# SCH_Usbhub.net
KiCad netlist of a schematic drawn in EasyEDA
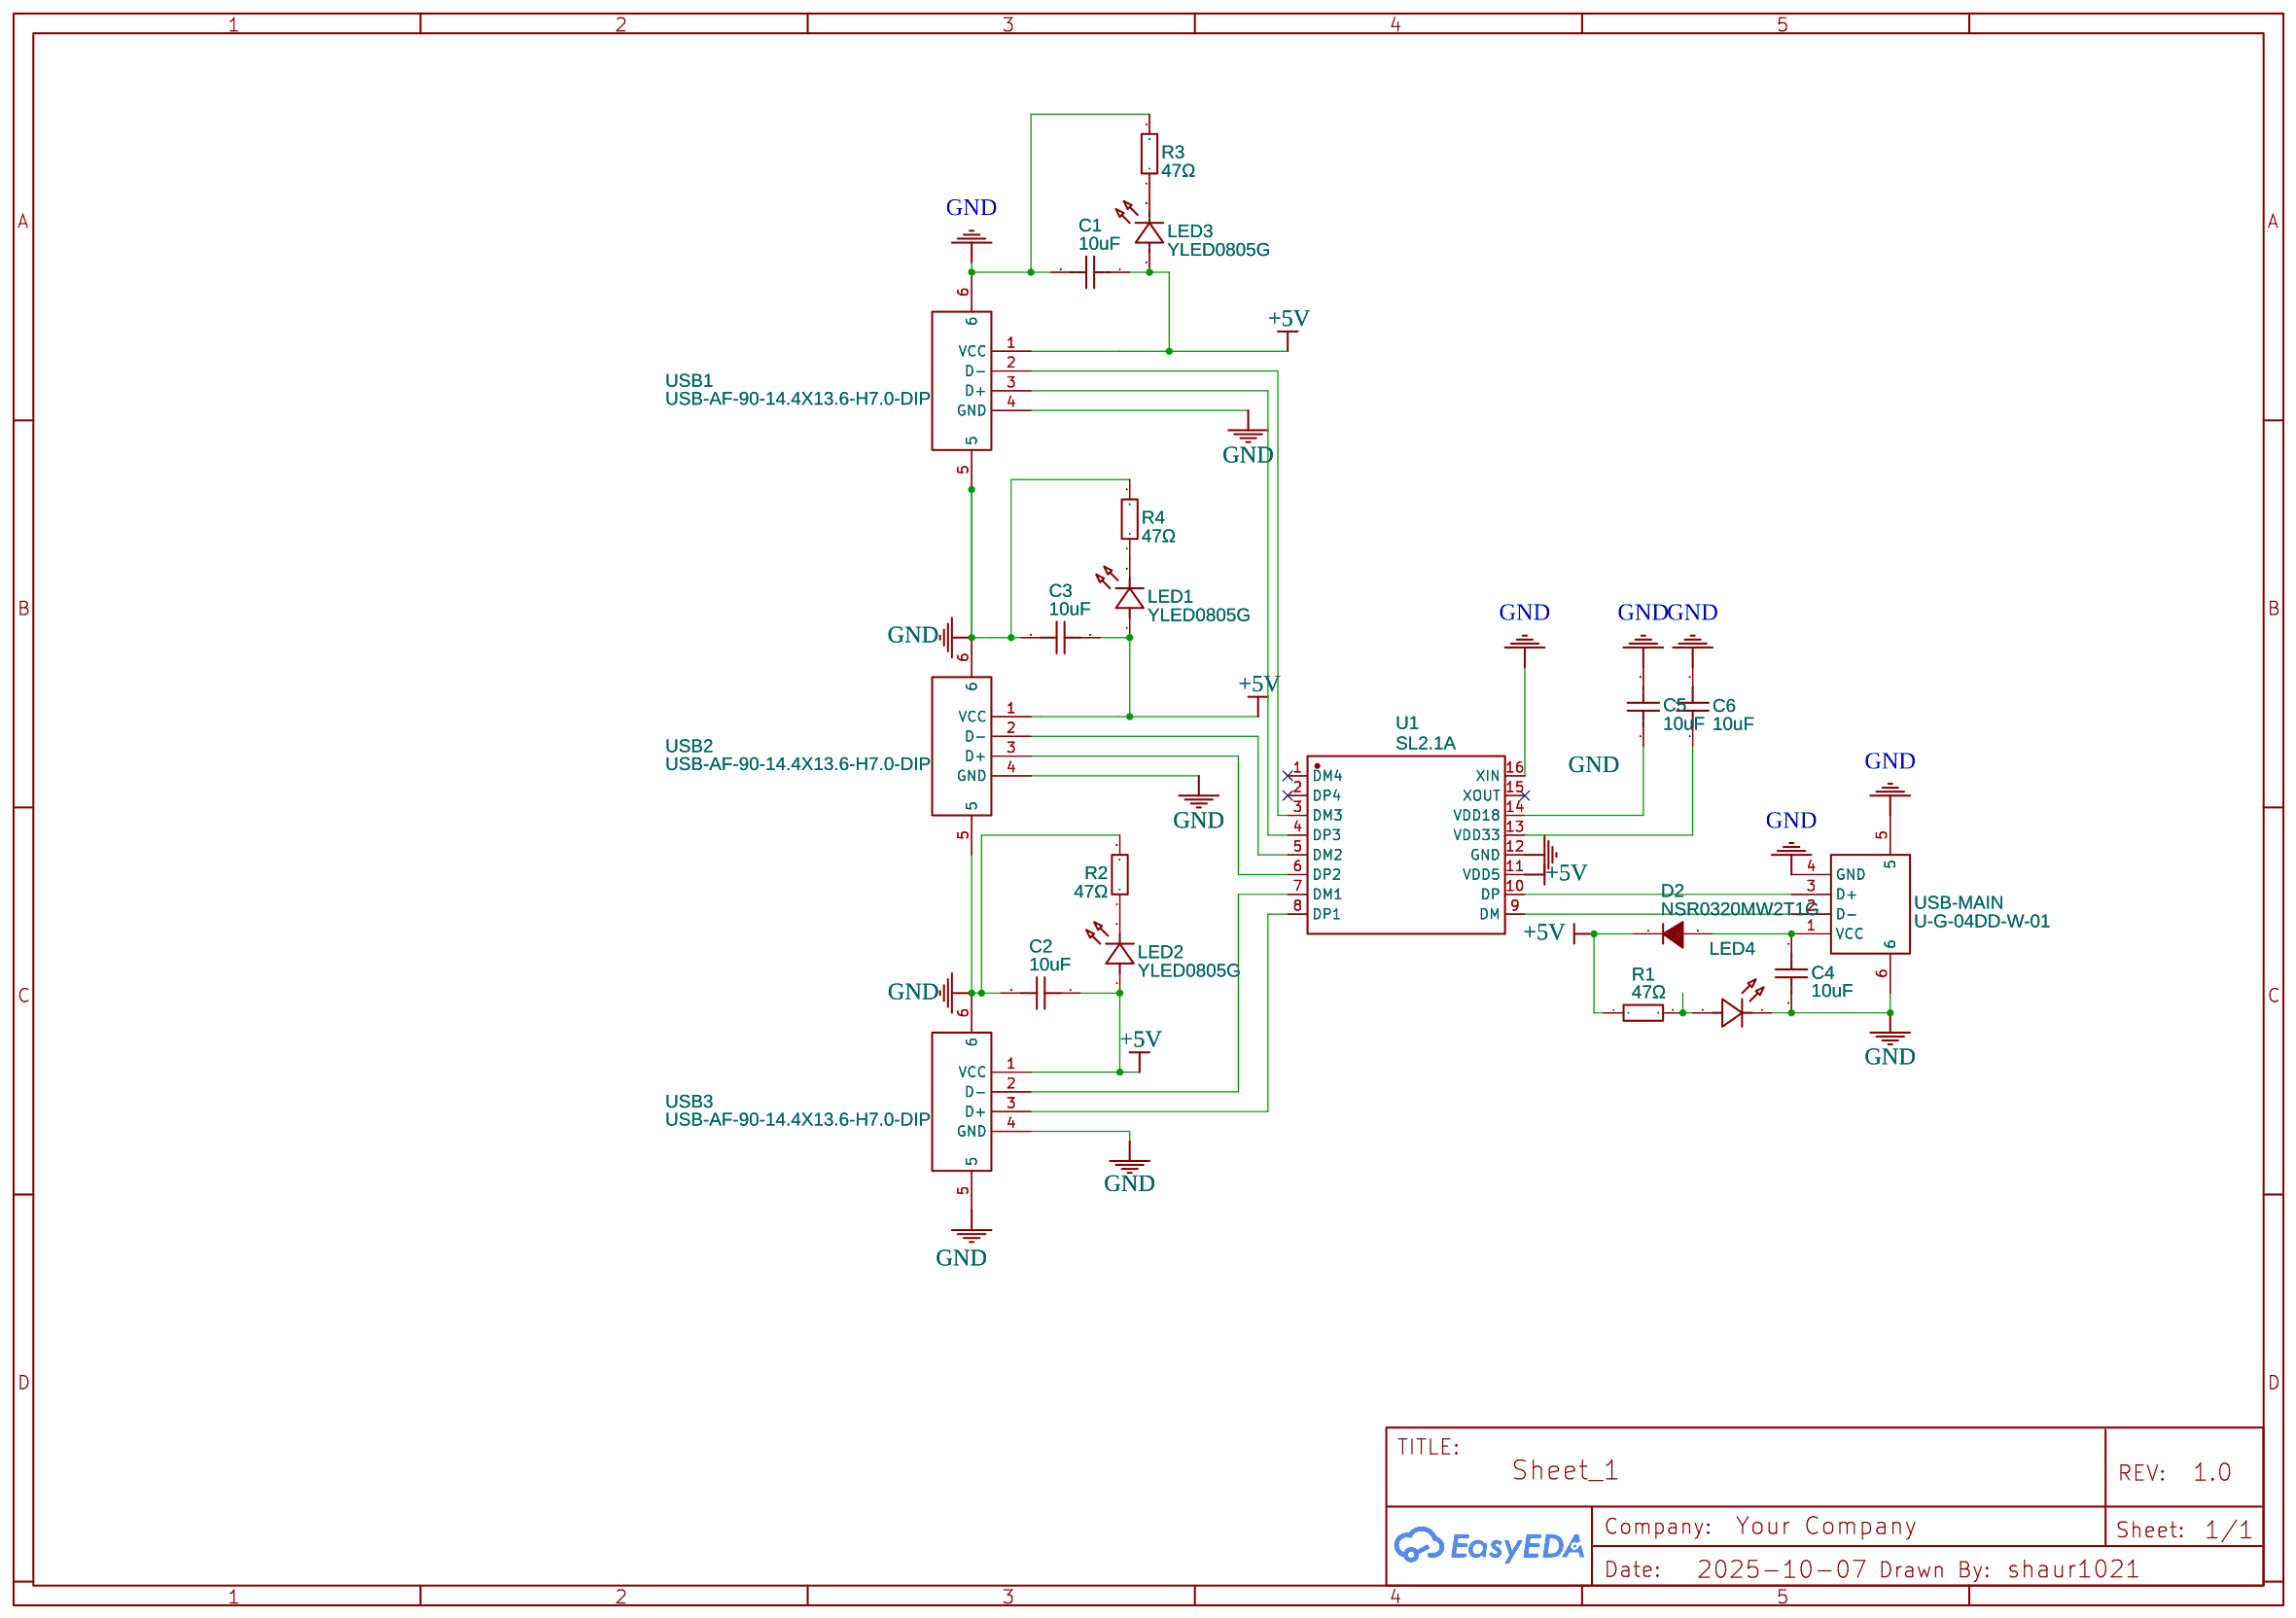
[diagram p0: schematic sheet]

(export (version "E")
  (design (tool "Eeschema 10.0.6"))
  (components
    (comp (ref "C1")
      (value "10uF")
      (fields
        (field (name "Manufacturer Part") "CL10A106KP8NNNC")
        (field (name "Manufacturer") "SAMSUNG(三星)")
      )
      (libsource (lib "") (part "CL10A106KP8NNNC"))
    )
    (comp (ref "C2")
      (value "10uF")
      (fields
        (field (name "Manufacturer Part") "CL10A106KP8NNNC")
        (field (name "Manufacturer") "SAMSUNG(三星)")
      )
      (libsource (lib "") (part "CL10A106KP8NNNC"))
    )
    (comp (ref "C3")
      (value "10uF")
      (fields
        (field (name "Manufacturer Part") "CL10A106KP8NNNC")
        (field (name "Manufacturer") "SAMSUNG(三星)")
      )
      (libsource (lib "") (part "CL10A106KP8NNNC"))
    )
    (comp (ref "C4")
      (value "10uF")
      (fields
        (field (name "Manufacturer Part") "CL10A106KP8NNNC")
        (field (name "Manufacturer") "SAMSUNG(三星)")
      )
      (libsource (lib "") (part "CL10A106KP8NNNC_1"))
    )
    (comp (ref "C5")
      (value "10uF")
      (fields
        (field (name "Manufacturer Part") "CL10A106KP8NNNC")
        (field (name "Manufacturer") "SAMSUNG(三星)")
      )
      (libsource (lib "") (part "CL10A106KP8NNNC_2"))
    )
    (comp (ref "C6")
      (value "10uF")
      (fields
        (field (name "Manufacturer Part") "CL10A106KP8NNNC")
        (field (name "Manufacturer") "SAMSUNG(三星)")
      )
      (libsource (lib "") (part "CL10A106KP8NNNC_2"))
    )
    (comp (ref "D2")
      (value "NSR0320MW2T1G")
      (fields (field (name "Manufacturer") "onsemi(安森美)"))
      (libsource (lib "") (part "NSR0320MW2T1G"))
    )
    (comp (ref "LED1")
      (value "YLED0805G")
      (fields (field (name "Manufacturer") "YONGYUTAI(永裕泰)"))
      (libsource (lib "") (part "YLED0805G"))
    )
    (comp (ref "LED2")
      (value "YLED0805G")
      (fields (field (name "Manufacturer") "YONGYUTAI(永裕泰)"))
      (libsource (lib "") (part "YLED0805G"))
    )
    (comp (ref "LED3")
      (value "YLED0805G")
      (fields (field (name "Manufacturer") "YONGYUTAI(永裕泰)"))
      (libsource (lib "") (part "YLED0805G"))
    )
    (comp (ref "LED4")
      (value "YLED0805G")
      (fields (field (name "Manufacturer") "YONGYUTAI(永裕泰)"))
      (libsource (lib "") (part "YLED0805G_1"))
    )
    (comp (ref "R1")
      (value "47Ω")
      (fields
        (field (name "Manufacturer Part") "0603WAF470JT5E")
        (field (name "Manufacturer") "UNI-ROYAL(厚声)")
      )
      (libsource (lib "") (part "0603WAF470JT5E_1"))
    )
    (comp (ref "R2")
      (value "47Ω")
      (fields
        (field (name "Manufacturer Part") "0603WAF470JT5E")
        (field (name "Manufacturer") "UNI-ROYAL(厚声)")
      )
      (libsource (lib "") (part "0603WAF470JT5E"))
    )
    (comp (ref "R3")
      (value "47Ω")
      (fields
        (field (name "Manufacturer Part") "0603WAF470JT5E")
        (field (name "Manufacturer") "UNI-ROYAL(厚声)")
      )
      (libsource (lib "") (part "0603WAF470JT5E"))
    )
    (comp (ref "R4")
      (value "47Ω")
      (fields
        (field (name "Manufacturer Part") "0603WAF470JT5E")
        (field (name "Manufacturer") "UNI-ROYAL(厚声)")
      )
      (libsource (lib "") (part "0603WAF470JT5E"))
    )
    (comp (ref "U1")
      (value "SL2.1A")
      (fields (field (name "Manufacturer") "CoreChips(和芯润德)"))
      (libsource (lib "") (part "SL2.1A"))
    )
    (comp (ref "USB-MAIN")
      (value "U-G-04DD-W-01")
      (fields (field (name "Manufacturer Part") "U-G-O4DD-W-1") (field (name "Manufacturer") "韩国韩荣"))
      (libsource (lib "") (part "U-G-04DD-W-01"))
    )
    (comp (ref "USB1")
      (value "USB-AF-90-14.4X13.6-H7.0-DIP")
      (fields (field (name "Manufacturer Part") "903-131A1011D10100") (field (name "Manufacturer") "精拓金"))
      (libsource (lib "") (part "USB-AF-90-14.4X13.6-H7.0-DIP"))
    )
    (comp (ref "USB2")
      (value "USB-AF-90-14.4X13.6-H7.0-DIP")
      (fields (field (name "Manufacturer Part") "903-131A1011D10100") (field (name "Manufacturer") "精拓金"))
      (libsource (lib "") (part "USB-AF-90-14.4X13.6-H7.0-DIP"))
    )
    (comp (ref "USB3")
      (value "USB-AF-90-14.4X13.6-H7.0-DIP")
      (fields (field (name "Manufacturer Part") "903-131A1011D10100") (field (name "Manufacturer") "精拓金"))
      (libsource (lib "") (part "USB-AF-90-14.4X13.6-H7.0-DIP"))
    )
  )
  (nets
    (net (code "1") (name "+5V") (class "Default")
      (node (ref "C1") (pin "1") (pinfunction "1_1") (pintype "unspecified"))
      (node (ref "C2") (pin "1") (pinfunction "1_1") (pintype "unspecified"))
      (node (ref "C3") (pin "1") (pinfunction "1_1") (pintype "unspecified"))
      (node (ref "D2") (pin "1") (pinfunction "C_1") (pintype "unspecified"))
      (node (ref "LED1") (pin "1") (pinfunction "A_1") (pintype "unspecified"))
      (node (ref "LED2") (pin "1") (pinfunction "A_1") (pintype "unspecified"))
      (node (ref "LED3") (pin "1") (pinfunction "A_1") (pintype "unspecified"))
      (node (ref "R1") (pin "1") (pinfunction "1_1") (pintype "input"))
      (node (ref "U1") (pin "11") (pinfunction "VDD5_11") (pintype "unspecified"))
      (node (ref "USB1") (pin "1") (pinfunction "VCC_1") (pintype "unspecified"))
      (node (ref "USB2") (pin "1") (pinfunction "VCC_1") (pintype "unspecified"))
      (node (ref "USB3") (pin "1") (pinfunction "VCC_1") (pintype "unspecified"))
    )
    (net (code "2") (name "GND") (class "Default")
      (node (ref "C1") (pin "2") (pinfunction "2_2") (pintype "unspecified"))
      (node (ref "C2") (pin "2") (pinfunction "2_2") (pintype "unspecified"))
      (node (ref "C3") (pin "2") (pinfunction "2_2") (pintype "unspecified"))
      (node (ref "C4") (pin "2") (pinfunction "2_2") (pintype "unspecified"))
      (node (ref "C5") (pin "2") (pinfunction "2_2") (pintype "unspecified"))
      (node (ref "C6") (pin "2") (pinfunction "2_2") (pintype "unspecified"))
      (node (ref "LED4") (pin "2") (pinfunction "K_2") (pintype "unspecified"))
      (node (ref "R2") (pin "2") (pinfunction "2_2") (pintype "input"))
      (node (ref "R3") (pin "2") (pinfunction "2_2") (pintype "input"))
      (node (ref "R4") (pin "2") (pinfunction "2_2") (pintype "input"))
      (node (ref "U1") (pin "12") (pinfunction "GND_12") (pintype "unspecified"))
      (node (ref "U1") (pin "16") (pinfunction "XIN_16") (pintype "unspecified"))
      (node (ref "USB-MAIN") (pin "4") (pinfunction "GND_4") (pintype "unspecified"))
      (node (ref "USB-MAIN") (pin "5") (pinfunction "5_5") (pintype "unspecified"))
      (node (ref "USB-MAIN") (pin "6") (pinfunction "6_6") (pintype "unspecified"))
      (node (ref "USB1") (pin "4") (pinfunction "GND_4") (pintype "unspecified"))
      (node (ref "USB1") (pin "5") (pinfunction "5_5") (pintype "unspecified"))
      (node (ref "USB1") (pin "6") (pinfunction "6_6") (pintype "unspecified"))
      (node (ref "USB2") (pin "4") (pinfunction "GND_4") (pintype "unspecified"))
      (node (ref "USB2") (pin "5") (pinfunction "5_5") (pintype "unspecified"))
      (node (ref "USB2") (pin "6") (pinfunction "6_6") (pintype "unspecified"))
      (node (ref "USB3") (pin "4") (pinfunction "GND_4") (pintype "unspecified"))
      (node (ref "USB3") (pin "5") (pinfunction "5_5") (pintype "unspecified"))
      (node (ref "USB3") (pin "6") (pinfunction "6_6") (pintype "unspecified"))
    )
    (net (code "3") (name "Net-(D2-A)") (class "Default")
      (node (ref "C4") (pin "1") (pinfunction "1_1") (pintype "unspecified"))
      (node (ref "D2") (pin "2") (pinfunction "A_2") (pintype "unspecified"))
      (node (ref "USB-MAIN") (pin "1") (pinfunction "VCC_1") (pintype "unspecified"))
    )
    (net (code "4") (name "Net-(LED1-K)") (class "Default")
      (node (ref "LED1") (pin "2") (pinfunction "K_2") (pintype "unspecified"))
      (node (ref "R4") (pin "1") (pinfunction "1_1") (pintype "input"))
    )
    (net (code "5") (name "Net-(LED2-K)") (class "Default")
      (node (ref "LED2") (pin "2") (pinfunction "K_2") (pintype "unspecified"))
      (node (ref "R2") (pin "1") (pinfunction "1_1") (pintype "input"))
    )
    (net (code "6") (name "Net-(LED3-K)") (class "Default")
      (node (ref "LED3") (pin "2") (pinfunction "K_2") (pintype "unspecified"))
      (node (ref "R3") (pin "1") (pinfunction "1_1") (pintype "input"))
    )
    (net (code "7") (name "Net-(LED4-A)") (class "Default")
      (node (ref "LED4") (pin "1") (pinfunction "A_1") (pintype "unspecified"))
      (node (ref "R1") (pin "2") (pinfunction "2_2") (pintype "input"))
    )
    (net (code "8") (name "Net-(U1-DM)") (class "Default")
      (node (ref "U1") (pin "9") (pinfunction "DM_9") (pintype "unspecified"))
      (node (ref "USB-MAIN") (pin "2") (pinfunction "D-_2") (pintype "unspecified"))
    )
    (net (code "9") (name "Net-(U1-DM1)") (class "Default")
      (node (ref "U1") (pin "7") (pinfunction "DM1_7") (pintype "unspecified"))
      (node (ref "USB3") (pin "2") (pinfunction "D-_2") (pintype "unspecified"))
    )
    (net (code "10") (name "Net-(U1-DM2)") (class "Default")
      (node (ref "U1") (pin "5") (pinfunction "DM2_5") (pintype "unspecified"))
      (node (ref "USB2") (pin "2") (pinfunction "D-_2") (pintype "unspecified"))
    )
    (net (code "11") (name "Net-(U1-DM3)") (class "Default")
      (node (ref "U1") (pin "3") (pinfunction "DM3_3") (pintype "unspecified"))
      (node (ref "USB1") (pin "2") (pinfunction "D-_2") (pintype "unspecified"))
    )
    (net (code "12") (name "Net-(U1-DP)") (class "Default")
      (node (ref "U1") (pin "10") (pinfunction "DP_10") (pintype "unspecified"))
      (node (ref "USB-MAIN") (pin "3") (pinfunction "D+_3") (pintype "unspecified"))
    )
    (net (code "13") (name "Net-(U1-DP1)") (class "Default")
      (node (ref "U1") (pin "8") (pinfunction "DP1_8") (pintype "unspecified"))
      (node (ref "USB3") (pin "3") (pinfunction "D+_3") (pintype "unspecified"))
    )
    (net (code "14") (name "Net-(U1-DP2)") (class "Default")
      (node (ref "U1") (pin "6") (pinfunction "DP2_6") (pintype "unspecified"))
      (node (ref "USB2") (pin "3") (pinfunction "D+_3") (pintype "unspecified"))
    )
    (net (code "15") (name "Net-(U1-DP3)") (class "Default")
      (node (ref "U1") (pin "4") (pinfunction "DP3_4") (pintype "unspecified"))
      (node (ref "USB1") (pin "3") (pinfunction "D+_3") (pintype "unspecified"))
    )
    (net (code "16") (name "Net-(U1-VDD18)") (class "Default")
      (node (ref "C5") (pin "1") (pinfunction "1_1") (pintype "unspecified"))
      (node (ref "U1") (pin "14") (pinfunction "VDD18_14") (pintype "unspecified"))
    )
    (net (code "17") (name "Net-(U1-VDD33)") (class "Default")
      (node (ref "C6") (pin "1") (pinfunction "1_1") (pintype "unspecified"))
      (node (ref "U1") (pin "13") (pinfunction "VDD33_13") (pintype "unspecified"))
    )
    (net (code "18") (name "unconnected-(U1-DM4-Pad1)") (class "Default")
      (node (ref "U1") (pin "1") (pinfunction "DM4_1") (pintype "unspecified+no_connect"))
    )
    (net (code "19") (name "unconnected-(U1-DP4-Pad2)") (class "Default")
      (node (ref "U1") (pin "2") (pinfunction "DP4_2") (pintype "unspecified+no_connect"))
    )
    (net (code "20") (name "unconnected-(U1-XOUT-Pad15)") (class "Default")
      (node (ref "U1") (pin "15") (pinfunction "XOUT_15") (pintype "unspecified+no_connect"))
    )
  )
)
